# ChakraPendantLEDs.net
KiCad netlist of a schematic drawn in EAGLE
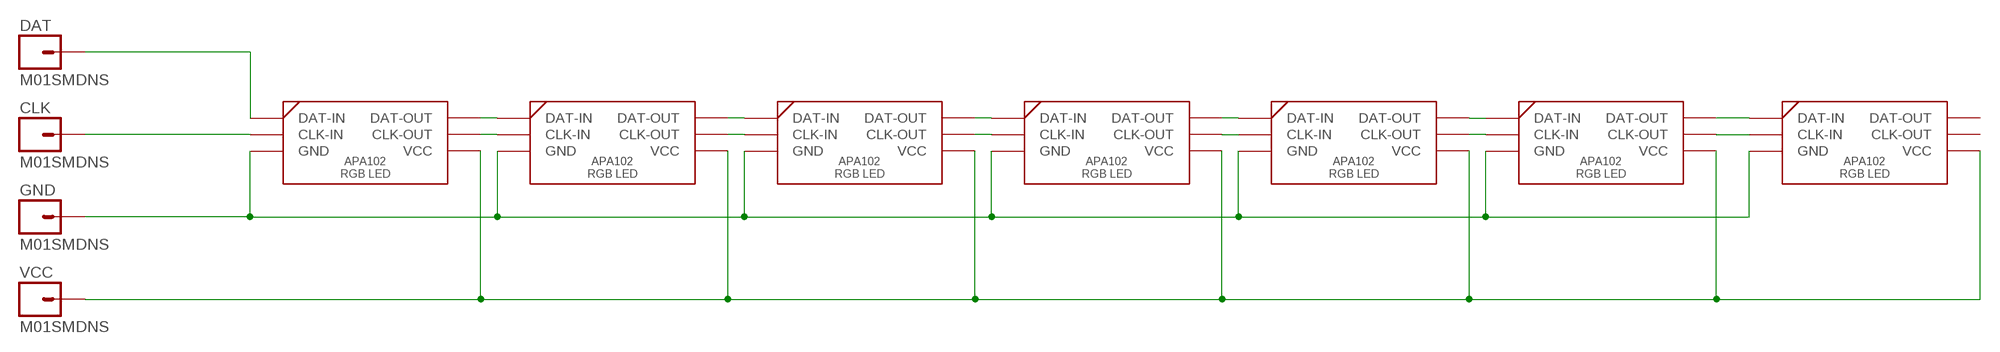
[diagram p0: schematic, sheet 1]

(export (version "E")
  (design (tool "Eeschema 10.0.6"))
  (components
    (comp (ref "CLK")
      (value "M01SMDNS")
      (footprint "eagle-import:1X01NS")
      (libsource (lib "eagle-import") (part "M01SMDNS"))
    )
    (comp (ref "DAT")
      (value "M01SMDNS")
      (footprint "eagle-import:1X01NS")
      (libsource (lib "eagle-import") (part "M01SMDNS"))
    )
    (comp (ref "GND")
      (value "M01SMDNS")
      (footprint "eagle-import:1X01NS")
      (libsource (lib "eagle-import") (part "M01SMDNS"))
    )
    (comp (ref "U$1")
      (value "APA102")
      (footprint "eagle-import:APA102_5050_LED")
      (libsource (lib "eagle-import") (part "APA102"))
    )
    (comp (ref "U$2")
      (value "APA102")
      (footprint "eagle-import:APA102_5050_LED")
      (libsource (lib "eagle-import") (part "APA102"))
    )
    (comp (ref "U$3")
      (value "APA102")
      (footprint "eagle-import:APA102_5050_LED")
      (libsource (lib "eagle-import") (part "APA102"))
    )
    (comp (ref "U$4")
      (value "APA102")
      (footprint "eagle-import:APA102_5050_LED")
      (libsource (lib "eagle-import") (part "APA102"))
    )
    (comp (ref "U$5")
      (value "APA102")
      (footprint "eagle-import:APA102_5050_LED")
      (libsource (lib "eagle-import") (part "APA102"))
    )
    (comp (ref "U$6")
      (value "APA102")
      (footprint "eagle-import:APA102_5050_LED")
      (libsource (lib "eagle-import") (part "APA102"))
    )
    (comp (ref "U$7")
      (value "APA102")
      (footprint "eagle-import:APA102_5050_LED")
      (libsource (lib "eagle-import") (part "APA102"))
    )
    (comp (ref "VCC")
      (value "M01SMDNS")
      (footprint "eagle-import:1X01NS")
      (libsource (lib "eagle-import") (part "M01SMDNS"))
    )
  )
  (nets
    (net (code "1") (name "Net-(CLK-Pad1)") (class "Default")
      (node (ref "CLK") (pin "1") (pinfunction "1_1") (pintype "passive"))
      (node (ref "U$1") (pin "CLK-IN") (pinfunction "CLK-IN_CLK-IN") (pintype "bidirectional"))
    )
    (net (code "2") (name "Net-(DAT-Pad1)") (class "Default")
      (node (ref "DAT") (pin "1") (pinfunction "1_1") (pintype "passive"))
      (node (ref "U$1") (pin "DAT-IN") (pinfunction "DAT-IN_DAT-IN") (pintype "bidirectional"))
    )
    (net (code "3") (name "Net-(GND-Pad1)") (class "Default")
      (node (ref "GND") (pin "1") (pinfunction "1_1") (pintype "passive"))
      (node (ref "U$1") (pin "GND") (pinfunction "GND_GND") (pintype "bidirectional"))
      (node (ref "U$2") (pin "GND") (pinfunction "GND_GND") (pintype "bidirectional"))
      (node (ref "U$3") (pin "GND") (pinfunction "GND_GND") (pintype "bidirectional"))
      (node (ref "U$4") (pin "GND") (pinfunction "GND_GND") (pintype "bidirectional"))
      (node (ref "U$5") (pin "GND") (pinfunction "GND_GND") (pintype "bidirectional"))
      (node (ref "U$6") (pin "GND") (pinfunction "GND_GND") (pintype "bidirectional"))
      (node (ref "U$7") (pin "GND") (pinfunction "GND_GND") (pintype "bidirectional"))
    )
    (net (code "4") (name "Net-(U$1-PadCLK-OUT)") (class "Default")
      (node (ref "U$1") (pin "CLK-OUT") (pinfunction "CLK-OUT_CLK-OUT") (pintype "bidirectional"))
      (node (ref "U$2") (pin "CLK-IN") (pinfunction "CLK-IN_CLK-IN") (pintype "bidirectional"))
    )
    (net (code "5") (name "Net-(U$1-PadDAT-OUT)") (class "Default")
      (node (ref "U$1") (pin "DAT-OUT") (pinfunction "DAT-OUT_DAT-OUT") (pintype "bidirectional"))
      (node (ref "U$2") (pin "DAT-IN") (pinfunction "DAT-IN_DAT-IN") (pintype "bidirectional"))
    )
    (net (code "6") (name "Net-(U$1-PadVCC)") (class "Default")
      (node (ref "U$1") (pin "VCC") (pinfunction "VCC_VCC") (pintype "bidirectional"))
      (node (ref "U$2") (pin "VCC") (pinfunction "VCC_VCC") (pintype "bidirectional"))
      (node (ref "U$3") (pin "VCC") (pinfunction "VCC_VCC") (pintype "bidirectional"))
      (node (ref "U$4") (pin "VCC") (pinfunction "VCC_VCC") (pintype "bidirectional"))
      (node (ref "U$5") (pin "VCC") (pinfunction "VCC_VCC") (pintype "bidirectional"))
      (node (ref "U$6") (pin "VCC") (pinfunction "VCC_VCC") (pintype "bidirectional"))
      (node (ref "U$7") (pin "VCC") (pinfunction "VCC_VCC") (pintype "bidirectional"))
      (node (ref "VCC") (pin "1") (pinfunction "1_1") (pintype "passive"))
    )
    (net (code "7") (name "Net-(U$2-PadCLK-OUT)") (class "Default")
      (node (ref "U$2") (pin "CLK-OUT") (pinfunction "CLK-OUT_CLK-OUT") (pintype "bidirectional"))
      (node (ref "U$3") (pin "CLK-IN") (pinfunction "CLK-IN_CLK-IN") (pintype "bidirectional"))
    )
    (net (code "8") (name "Net-(U$2-PadDAT-OUT)") (class "Default")
      (node (ref "U$2") (pin "DAT-OUT") (pinfunction "DAT-OUT_DAT-OUT") (pintype "bidirectional"))
      (node (ref "U$3") (pin "DAT-IN") (pinfunction "DAT-IN_DAT-IN") (pintype "bidirectional"))
    )
    (net (code "9") (name "Net-(U$3-PadCLK-OUT)") (class "Default")
      (node (ref "U$3") (pin "CLK-OUT") (pinfunction "CLK-OUT_CLK-OUT") (pintype "bidirectional"))
      (node (ref "U$4") (pin "CLK-IN") (pinfunction "CLK-IN_CLK-IN") (pintype "bidirectional"))
    )
    (net (code "10") (name "Net-(U$3-PadDAT-OUT)") (class "Default")
      (node (ref "U$3") (pin "DAT-OUT") (pinfunction "DAT-OUT_DAT-OUT") (pintype "bidirectional"))
      (node (ref "U$4") (pin "DAT-IN") (pinfunction "DAT-IN_DAT-IN") (pintype "bidirectional"))
    )
    (net (code "11") (name "Net-(U$4-PadCLK-OUT)") (class "Default")
      (node (ref "U$4") (pin "CLK-OUT") (pinfunction "CLK-OUT_CLK-OUT") (pintype "bidirectional"))
      (node (ref "U$5") (pin "CLK-IN") (pinfunction "CLK-IN_CLK-IN") (pintype "bidirectional"))
    )
    (net (code "12") (name "Net-(U$4-PadDAT-OUT)") (class "Default")
      (node (ref "U$4") (pin "DAT-OUT") (pinfunction "DAT-OUT_DAT-OUT") (pintype "bidirectional"))
      (node (ref "U$5") (pin "DAT-IN") (pinfunction "DAT-IN_DAT-IN") (pintype "bidirectional"))
    )
    (net (code "13") (name "Net-(U$5-PadCLK-OUT)") (class "Default")
      (node (ref "U$5") (pin "CLK-OUT") (pinfunction "CLK-OUT_CLK-OUT") (pintype "bidirectional"))
      (node (ref "U$6") (pin "CLK-IN") (pinfunction "CLK-IN_CLK-IN") (pintype "bidirectional"))
    )
    (net (code "14") (name "Net-(U$5-PadDAT-OUT)") (class "Default")
      (node (ref "U$5") (pin "DAT-OUT") (pinfunction "DAT-OUT_DAT-OUT") (pintype "bidirectional"))
      (node (ref "U$6") (pin "DAT-IN") (pinfunction "DAT-IN_DAT-IN") (pintype "bidirectional"))
    )
    (net (code "15") (name "Net-(U$6-PadCLK-OUT)") (class "Default")
      (node (ref "U$6") (pin "CLK-OUT") (pinfunction "CLK-OUT_CLK-OUT") (pintype "bidirectional"))
      (node (ref "U$7") (pin "CLK-IN") (pinfunction "CLK-IN_CLK-IN") (pintype "bidirectional"))
    )
    (net (code "16") (name "Net-(U$6-PadDAT-OUT)") (class "Default")
      (node (ref "U$6") (pin "DAT-OUT") (pinfunction "DAT-OUT_DAT-OUT") (pintype "bidirectional"))
      (node (ref "U$7") (pin "DAT-IN") (pinfunction "DAT-IN_DAT-IN") (pintype "bidirectional"))
    )
    (net (code "17") (name "unconnected-(U$7-PadCLK-OUT)") (class "Default")
      (node (ref "U$7") (pin "CLK-OUT") (pinfunction "CLK-OUT_CLK-OUT") (pintype "bidirectional"))
    )
    (net (code "18") (name "unconnected-(U$7-PadDAT-OUT)") (class "Default")
      (node (ref "U$7") (pin "DAT-OUT") (pinfunction "DAT-OUT_DAT-OUT") (pintype "bidirectional"))
    )
  )
)
